# prom_dual.net
KiCad netlist of a schematic drawn in Altium Designer
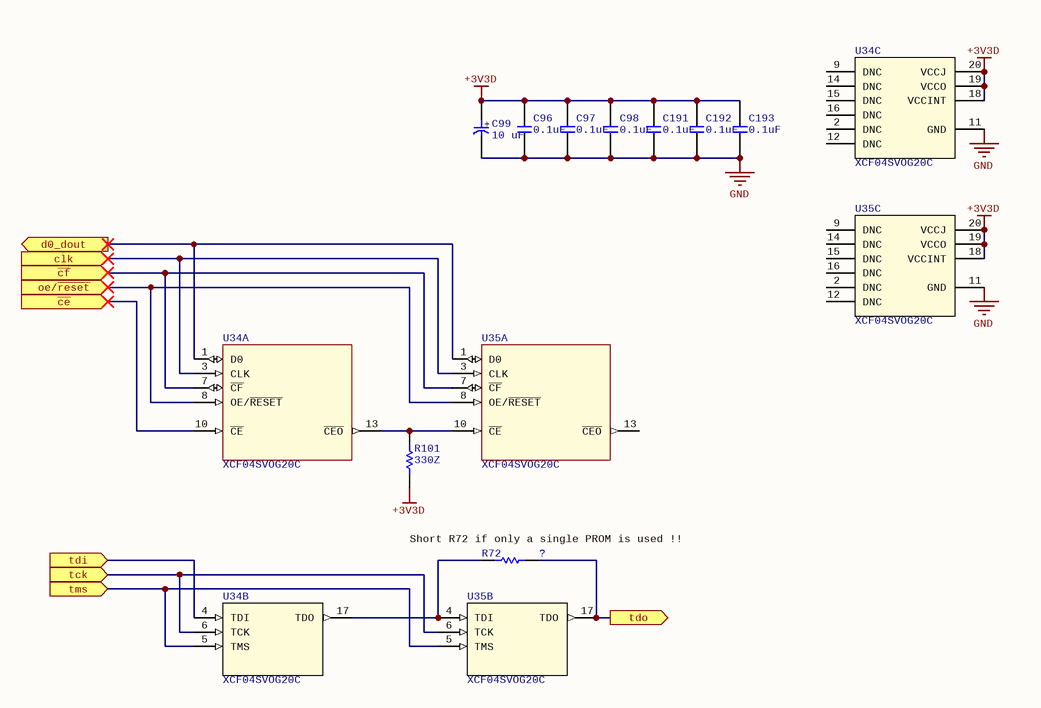
[diagram p0: prom_dual.SchDoc]

(export (version "E")
  (design (tool "Eeschema 10.0.6"))
  (components
    (comp (ref "C96")
      (value "0.1uF")
      (footprint "C0603")
      (description "CAP2, CER, 0.1uF, 10%, 50V, 0603, X7R")
      (fields
        (field (name "MANUFACTURER") "AVX Corporation")
        (field (name "MANUFACTURER PART NUMBER") "06035C104KAT2A")
      )
      (libsource (lib "stdlib") (part "CAP/06035C104KAT2A"))
    )
    (comp (ref "C97")
      (value "0.1uF")
      (footprint "C0603")
      (description "CAP2, CER, 0.1uF, 10%, 50V, 0603, X7R")
      (fields
        (field (name "MANUFACTURER") "AVX Corporation")
        (field (name "MANUFACTURER PART NUMBER") "06035C104KAT2A")
      )
      (libsource (lib "stdlib") (part "CAP/06035C104KAT2A"))
    )
    (comp (ref "C98")
      (value "0.1uF")
      (footprint "C0603")
      (description "CAP2, CER, 0.1uF, 10%, 50V, 0603, X7R")
      (fields
        (field (name "MANUFACTURER") "AVX Corporation")
        (field (name "MANUFACTURER PART NUMBER") "06035C104KAT2A")
      )
      (libsource (lib "stdlib") (part "CAP/06035C104KAT2A"))
    )
    (comp (ref "C99")
      (value "10 uF")
      (footprint "KEMET 1206")
      (description "CAP2, TANT,  10uF, 10%, 10V, 1206")
      (fields
        (field (name "MANUFACTURER") "Kemet")
        (field (name "MANUFACTURER PART NUMBER") "T491A106K010AT")
      )
      (libsource (lib "stdlib") (part "Kemet/T491A106K010AT"))
    )
    (comp (ref "C191")
      (value "0.1uF")
      (footprint "C0603")
      (description "CAP2, CER, 0.1uF, 10%, 50V, 0603, X7R")
      (fields
        (field (name "MANUFACTURER") "AVX Corporation")
        (field (name "MANUFACTURER PART NUMBER") "06035C104KAT2A")
      )
      (libsource (lib "stdlib") (part "CAP/06035C104KAT2A"))
    )
    (comp (ref "C192")
      (value "0.1uF")
      (footprint "C0603")
      (description "CAP2, CER, 0.1uF, 10%, 50V, 0603, X7R")
      (fields
        (field (name "MANUFACTURER") "AVX Corporation")
        (field (name "MANUFACTURER PART NUMBER") "06035C104KAT2A")
      )
      (libsource (lib "stdlib") (part "CAP/06035C104KAT2A"))
    )
    (comp (ref "C193")
      (value "0.1uF")
      (footprint "C0603")
      (description "CAP2, CER, 0.1uF, 10%, 50V, 0603, X7R")
      (fields
        (field (name "MANUFACTURER") "AVX Corporation")
        (field (name "MANUFACTURER PART NUMBER") "06035C104KAT2A")
      )
      (libsource (lib "stdlib") (part "CAP/06035C104KAT2A"))
    )
    (comp (ref "R72")
      (value "?")
      (footprint "R0805")
      (description "Placeholder")
      (libsource (lib "stdlib") (part "RES SMD ? OHM 1% 1/10W 0805"))
    )
    (comp (ref "R101")
      (value "330Z")
      (footprint "R0603")
      (description "RES0, SMD,  330Z, 1.0%, 1/10W, 0603")
      (fields
        (field (name "MANUFACTURER") "Rohm Semiconductor")
        (field (name "MANUFACTURER PART NUMBER") "MCR03ERTF3300")
      )
      (libsource (lib "stdlib") (part "CRCW0603330RFKEA"))
    )
    (comp (ref "U34")
      (value "XCF04SVOG20C")
      (footprint "R-PDSO-G20")
      (description "PROM, 4M GATE, Platform Flash")
      (libsource (lib "stdlib") (part "XCF04SVOG20C TSSOP-20"))
    )
    (comp (ref "U35")
      (value "XCF04SVOG20C")
      (footprint "R-PDSO-G20")
      (description "PROM, 4M GATE, Platform Flash")
      (libsource (lib "stdlib") (part "XCF04SVOG20C TSSOP-20"))
    )
  )
  (nets
    (net (code "1") (name "+3V3D") (class "Default")
      (node (ref "C191") (pin "2") (pinfunction "2_2") (pintype "passive"))
      (node (ref "C192") (pin "2") (pinfunction "2_2") (pintype "passive"))
      (node (ref "C193") (pin "2") (pinfunction "2_2") (pintype "passive"))
      (node (ref "C96") (pin "2") (pinfunction "2_2") (pintype "passive"))
      (node (ref "C97") (pin "2") (pinfunction "2_2") (pintype "passive"))
      (node (ref "C98") (pin "2") (pinfunction "2_2") (pintype "passive"))
      (node (ref "C99") (pin "1") (pinfunction "+_1") (pintype "passive"))
      (node (ref "R101") (pin "1") (pinfunction "1_1") (pintype "passive"))
      (node (ref "U34") (pin "18") (pinfunction "VCCINT_18") (pintype "power_in"))
      (node (ref "U34") (pin "19") (pinfunction "VCCO_19") (pintype "power_in"))
      (node (ref "U34") (pin "20") (pinfunction "VCCJ_20") (pintype "power_in"))
      (node (ref "U35") (pin "18") (pinfunction "VCCINT_18") (pintype "power_in"))
      (node (ref "U35") (pin "19") (pinfunction "VCCO_19") (pintype "power_in"))
      (node (ref "U35") (pin "20") (pinfunction "VCCJ_20") (pintype "power_in"))
    )
    (net (code "2") (name "/clk") (class "Default")
      (node (ref "U34") (pin "3") (pinfunction "CLK_3") (pintype "input"))
      (node (ref "U35") (pin "3") (pinfunction "CLK_3") (pintype "input"))
    )
    (net (code "3") (name "/d0_dout") (class "Default")
      (node (ref "U34") (pin "1") (pinfunction "D0_1") (pintype "bidirectional"))
      (node (ref "U35") (pin "1") (pinfunction "D0_1") (pintype "bidirectional"))
    )
    (net (code "4") (name "/oe{slash}~{reset}") (class "Default")
      (node (ref "U34") (pin "8") (pinfunction "OE/~{RESET}_8") (pintype "input"))
      (node (ref "U35") (pin "8") (pinfunction "OE/~{RESET}_8") (pintype "input"))
    )
    (net (code "5") (name "/tck") (class "Default")
      (node (ref "U34") (pin "6") (pinfunction "TCK_6") (pintype "input"))
      (node (ref "U35") (pin "6") (pinfunction "TCK_6") (pintype "input"))
    )
    (net (code "6") (name "/tdi") (class "Default")
      (node (ref "U34") (pin "4") (pinfunction "TDI_4") (pintype "input"))
    )
    (net (code "7") (name "/tdo") (class "Default")
      (node (ref "R72") (pin "2") (pinfunction "2_2") (pintype "passive"))
      (node (ref "U35") (pin "17") (pinfunction "TDO_17") (pintype "output"))
    )
    (net (code "8") (name "/tms") (class "Default")
      (node (ref "U34") (pin "5") (pinfunction "TMS_5") (pintype "input"))
      (node (ref "U35") (pin "5") (pinfunction "TMS_5") (pintype "input"))
    )
    (net (code "9") (name "/~{ce}") (class "Default")
      (node (ref "U34") (pin "10") (pinfunction "~{CE}_10") (pintype "input+no_connect"))
    )
    (net (code "10") (name "/~{cf}") (class "Default")
      (node (ref "U34") (pin "7") (pinfunction "~{CF}_7") (pintype "bidirectional"))
      (node (ref "U35") (pin "7") (pinfunction "~{CF}_7") (pintype "bidirectional"))
    )
    (net (code "11") (name "GND") (class "Default")
      (node (ref "C191") (pin "1") (pinfunction "5_1") (pintype "passive"))
      (node (ref "C192") (pin "1") (pinfunction "5_1") (pintype "passive"))
      (node (ref "C193") (pin "1") (pinfunction "5_1") (pintype "passive"))
      (node (ref "C96") (pin "1") (pinfunction "5_1") (pintype "passive"))
      (node (ref "C97") (pin "1") (pinfunction "5_1") (pintype "passive"))
      (node (ref "C98") (pin "1") (pinfunction "5_1") (pintype "passive"))
      (node (ref "C99") (pin "2") (pinfunction "-_2") (pintype "passive"))
      (node (ref "U34") (pin "11") (pinfunction "GND_11") (pintype "power_in"))
      (node (ref "U35") (pin "11") (pinfunction "GND_11") (pintype "power_in"))
    )
    (net (code "12") (name "Net-(U34A-~{CEO})") (class "Default")
      (node (ref "R101") (pin "2") (pinfunction "2_2") (pintype "passive"))
      (node (ref "U34") (pin "13") (pinfunction "~{CEO}_13") (pintype "output"))
      (node (ref "U35") (pin "10") (pinfunction "~{CE}_10") (pintype "input"))
    )
    (net (code "13") (name "Net-(U34B-TDO)") (class "Default")
      (node (ref "R72") (pin "1") (pinfunction "1_1") (pintype "passive"))
      (node (ref "U34") (pin "17") (pinfunction "TDO_17") (pintype "output"))
      (node (ref "U35") (pin "4") (pinfunction "TDI_4") (pintype "input"))
    )
    (net (code "14") (name "unconnected-(U34C-DNC-Pad2)") (class "Default")
      (node (ref "U34") (pin "2") (pinfunction "DNC_2") (pintype "passive"))
    )
    (net (code "15") (name "unconnected-(U34C-DNC-Pad9)") (class "Default")
      (node (ref "U34") (pin "9") (pinfunction "DNC_9") (pintype "passive"))
    )
    (net (code "16") (name "unconnected-(U34C-DNC-Pad12)") (class "Default")
      (node (ref "U34") (pin "12") (pinfunction "DNC_12") (pintype "passive"))
    )
    (net (code "17") (name "unconnected-(U34C-DNC-Pad14)") (class "Default")
      (node (ref "U34") (pin "14") (pinfunction "DNC_14") (pintype "passive"))
    )
    (net (code "18") (name "unconnected-(U34C-DNC-Pad15)") (class "Default")
      (node (ref "U34") (pin "15") (pinfunction "DNC_15") (pintype "passive"))
    )
    (net (code "19") (name "unconnected-(U34C-DNC-Pad16)") (class "Default")
      (node (ref "U34") (pin "16") (pinfunction "DNC_16") (pintype "passive"))
    )
    (net (code "20") (name "unconnected-(U35A-~{CEO}-Pad13)") (class "Default")
      (node (ref "U35") (pin "13") (pinfunction "~{CEO}_13") (pintype "output"))
    )
    (net (code "21") (name "unconnected-(U35C-DNC-Pad2)") (class "Default")
      (node (ref "U35") (pin "2") (pinfunction "DNC_2") (pintype "passive"))
    )
    (net (code "22") (name "unconnected-(U35C-DNC-Pad9)") (class "Default")
      (node (ref "U35") (pin "9") (pinfunction "DNC_9") (pintype "passive"))
    )
    (net (code "23") (name "unconnected-(U35C-DNC-Pad12)") (class "Default")
      (node (ref "U35") (pin "12") (pinfunction "DNC_12") (pintype "passive"))
    )
    (net (code "24") (name "unconnected-(U35C-DNC-Pad14)") (class "Default")
      (node (ref "U35") (pin "14") (pinfunction "DNC_14") (pintype "passive"))
    )
    (net (code "25") (name "unconnected-(U35C-DNC-Pad15)") (class "Default")
      (node (ref "U35") (pin "15") (pinfunction "DNC_15") (pintype "passive"))
    )
    (net (code "26") (name "unconnected-(U35C-DNC-Pad16)") (class "Default")
      (node (ref "U35") (pin "16") (pinfunction "DNC_16") (pintype "passive"))
    )
  )
)
